# Adafruit_Bluefruit_LE_SPI_Friend.net
KiCad netlist of a schematic drawn in EAGLE
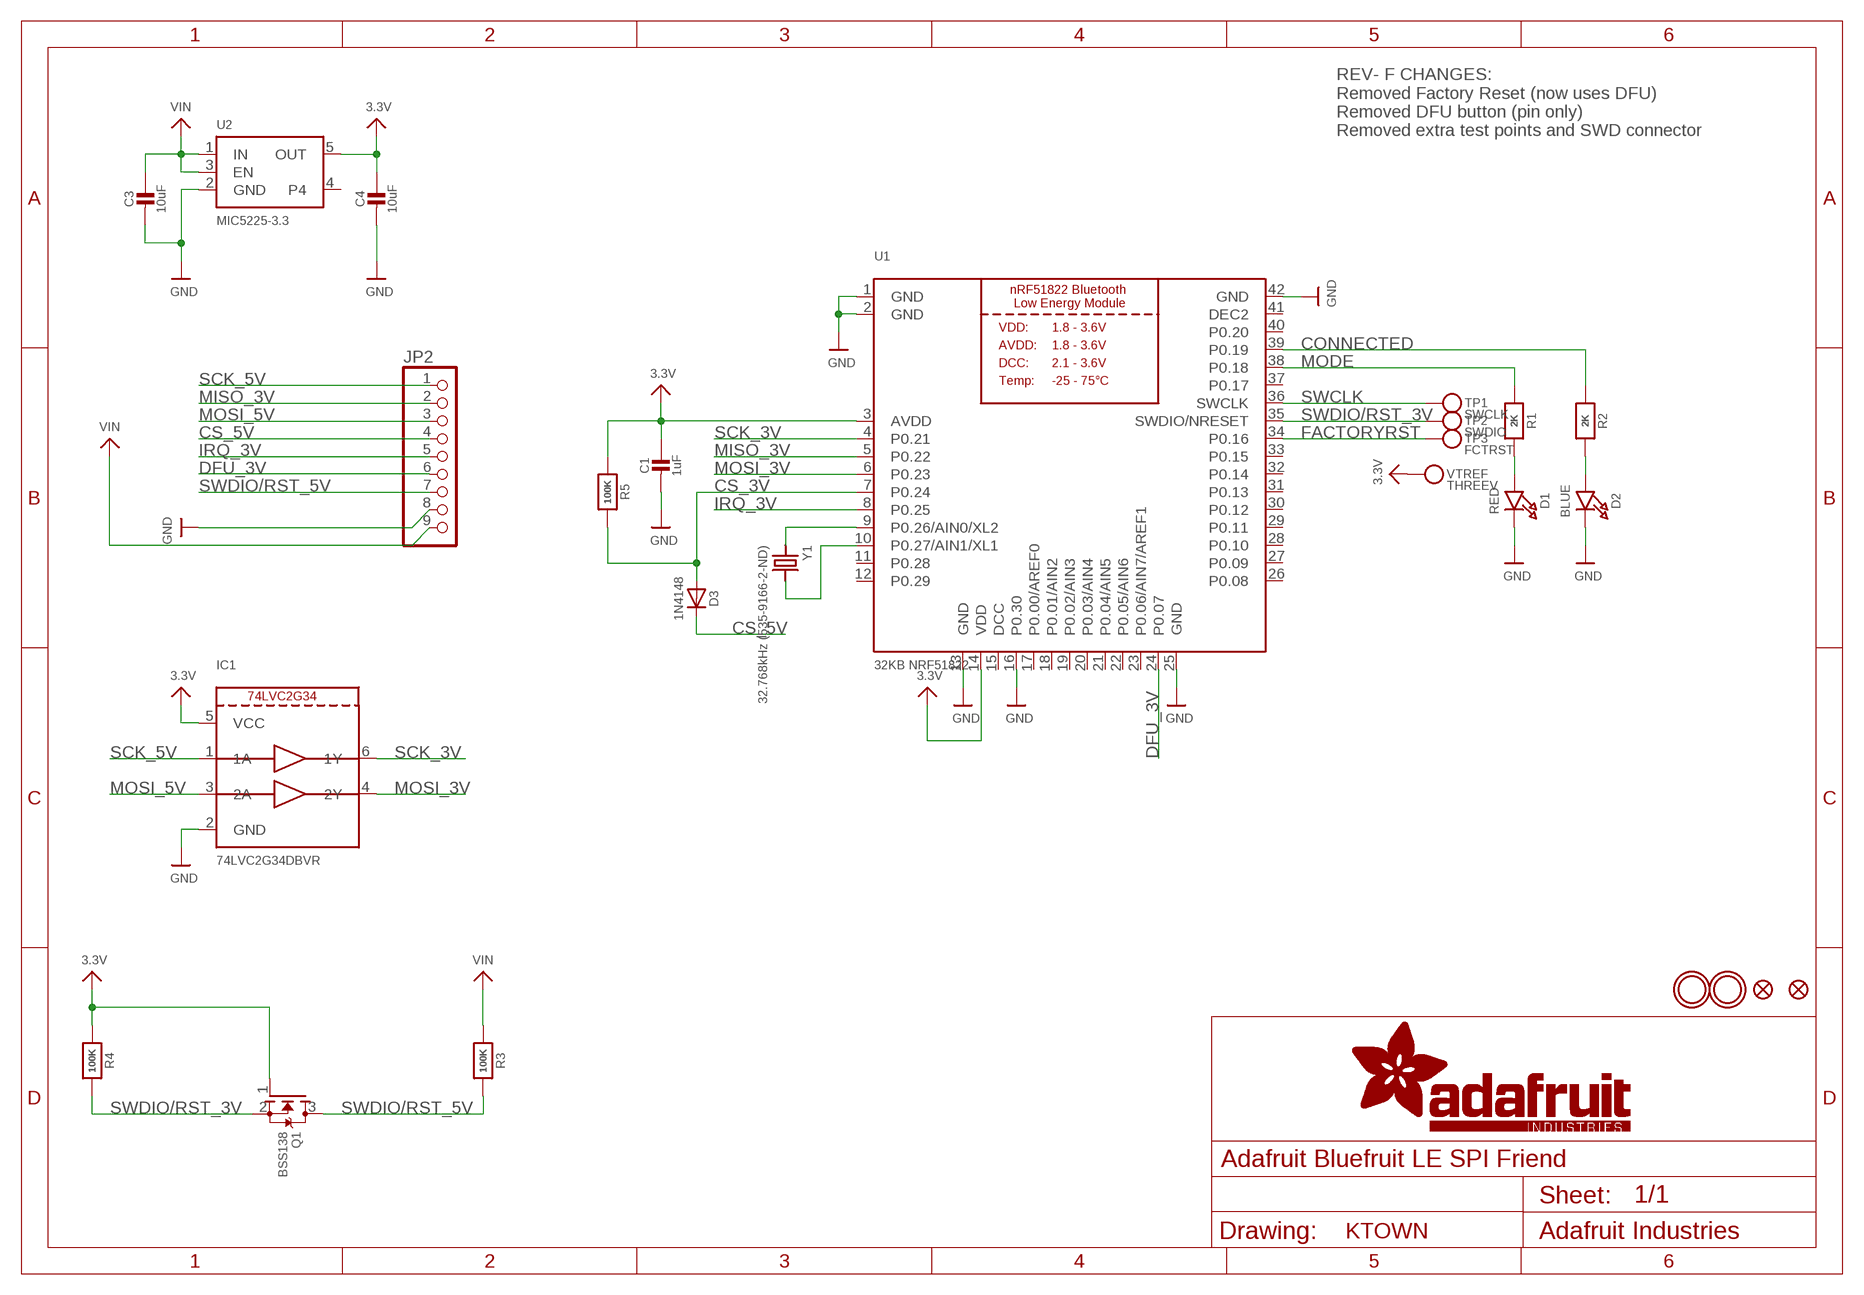
[diagram p0: schematic, sheet 1]

(export (version "E")
  (design (tool "Eeschema 10.0.6"))
  (components
    (comp (ref "C1")
      (value "1uF")
      (footprint "eagle-import:0805_10MGAP")
      (libsource (lib "eagle-import") (part "CAP_CERAMIC0805_10MGAP"))
    )
    (comp (ref "C3")
      (value "10uF")
      (footprint "eagle-import:0805-NO")
      (libsource (lib "eagle-import") (part "CAP_CERAMIC0805-NOOUTLINE"))
    )
    (comp (ref "C4")
      (value "10uF")
      (footprint "eagle-import:0805_10MGAP")
      (libsource (lib "eagle-import") (part "CAP_CERAMIC0805_10MGAP"))
    )
    (comp (ref "D1")
      (value "RED")
      (footprint "eagle-import:CHIPLED_0805_NOOUTLINE")
      (libsource (lib "eagle-import") (part "LED0805_NOOUTLINE"))
    )
    (comp (ref "D2")
      (value "BLUE")
      (footprint "eagle-import:CHIPLED_0805_NOOUTLINE")
      (libsource (lib "eagle-import") (part "LED0805_NOOUTLINE"))
    )
    (comp (ref "D3")
      (value "1N4148")
      (footprint "eagle-import:SOD-323")
      (libsource (lib "eagle-import") (part "DIODESOD-323"))
    )
    (comp (ref "FID1")
      (value "FIDUCIAL\"\"")
      (footprint "eagle-import:FIDUCIAL_1MM")
      (libsource (lib "eagle-import") (part "FIDUCIAL{dblquote}{dblquote}"))
    )
    (comp (ref "FID3")
      (value "FIDUCIAL\"\"")
      (footprint "eagle-import:FIDUCIAL_1MM")
      (libsource (lib "eagle-import") (part "FIDUCIAL{dblquote}{dblquote}"))
    )
    (comp (ref "IC1")
      (value "74LVC2G34DBVR")
      (footprint "eagle-import:SOT23-6")
      (libsource (lib "eagle-import") (part "74LVC2G34DBVR"))
    )
    (comp (ref "JP2")
      (value "HEADER-1X970MIL")
      (footprint "eagle-import:1X09_ROUND_70")
      (libsource (lib "eagle-import") (part "HEADER-1X970MIL"))
    )
    (comp (ref "Q1")
      (value "BSS138")
      (footprint "eagle-import:SOT23-WIDE@1")
      (libsource (lib "eagle-import") (part "MOSFET-NWIDE"))
    )
    (comp (ref "R1")
      (value "2K")
      (footprint "eagle-import:_0805MP")
      (libsource (lib "eagle-import") (part "RESISTOR_0805MP"))
    )
    (comp (ref "R2")
      (value "2K")
      (footprint "eagle-import:_0805MP")
      (libsource (lib "eagle-import") (part "RESISTOR_0805MP"))
    )
    (comp (ref "R3")
      (value "100K")
      (footprint "eagle-import:0805-NO")
      (libsource (lib "eagle-import") (part "RESISTOR0805_NOOUTLINE"))
    )
    (comp (ref "R4")
      (value "100K")
      (footprint "eagle-import:0805-NO")
      (libsource (lib "eagle-import") (part "RESISTOR0805_NOOUTLINE"))
    )
    (comp (ref "R5")
      (value "100K")
      (footprint "eagle-import:_0805MP")
      (libsource (lib "eagle-import") (part "RESISTOR_0805MP"))
    )
    (comp (ref "TP1")
      (value "SWCLK")
      (footprint "eagle-import:PAD-1.5X2.0")
      (libsource (lib "eagle-import") (part "TESTPOINT1.5X2.0MM_NOCREAM"))
    )
    (comp (ref "TP2")
      (value "SWDIO")
      (footprint "eagle-import:PAD-1.5X2.0")
      (libsource (lib "eagle-import") (part "TESTPOINT1.5X2.0MM_NOCREAM"))
    )
    (comp (ref "TP3")
      (value "FCTRST")
      (footprint "eagle-import:PAD-1.5X2.0")
      (libsource (lib "eagle-import") (part "TESTPOINT1.5X2.0MM_NOCREAM"))
    )
    (comp (ref "U$28")
      (value "MOUNTINGHOLE2.5")
      (footprint "eagle-import:MOUNTINGHOLE_2.5_PLATED")
      (libsource (lib "eagle-import") (part "MOUNTINGHOLE2.5"))
    )
    (comp (ref "U$29")
      (value "MOUNTINGHOLE2.5")
      (footprint "eagle-import:MOUNTINGHOLE_2.5_PLATED")
      (libsource (lib "eagle-import") (part "MOUNTINGHOLE2.5"))
    )
    (comp (ref "U1")
      (value "32KB NRF51822")
      (footprint "eagle-import:BLE_MODULE_RAYTAC_MDBT40")
      (libsource (lib "eagle-import") (part "NRF51822_MODULE_MDBT40"))
    )
    (comp (ref "U2")
      (value "MIC5225-3.3")
      (footprint "eagle-import:SOT23-5")
      (libsource (lib "eagle-import") (part "VREG_SOT23-5"))
    )
    (comp (ref "VTREF")
      (value "THREEV")
      (footprint "eagle-import:PAD-1.5X2.0")
      (libsource (lib "eagle-import") (part "TESTPOINT1.5X2.0MM_NOCREAM"))
    )
    (comp (ref "Y1")
      (value "32.768kHz (535-9166-2-ND)")
      (footprint "eagle-import:CRYSTAL_CYL_2X6MM_SMT")
      (libsource (lib "eagle-import") (part "CRYSTAL2.0X6.0_32.768"))
    )
  )
  (nets
    (net (code "1") (name "/CONNECTED") (class "Default")
      (node (ref "R2") (pin "1") (pinfunction "1_1") (pintype "passive"))
      (node (ref "U1") (pin "39") (pinfunction "P0.19_39") (pintype "bidirectional"))
    )
    (net (code "2") (name "/CS_3V") (class "Default")
      (node (ref "D3") (pin "A") (pinfunction "A_A") (pintype "passive"))
      (node (ref "R5") (pin "2") (pinfunction "2_2") (pintype "passive"))
      (node (ref "U1") (pin "7") (pinfunction "P0.24_7") (pintype "bidirectional"))
    )
    (net (code "3") (name "/CS_5V") (class "Default")
      (node (ref "D3") (pin "C") (pinfunction "C_C") (pintype "passive"))
      (node (ref "JP2") (pin "4") (pinfunction "4_4") (pintype "passive"))
    )
    (net (code "4") (name "/DCC") (class "Default")
      (node (ref "U1") (pin "15") (pinfunction "DCC_15") (pintype "power_in"))
    )
    (net (code "5") (name "/DEC2") (class "Default")
      (node (ref "U1") (pin "41") (pinfunction "DEC2_41") (pintype "power_in"))
    )
    (net (code "6") (name "/DFU_3V") (class "Default")
      (node (ref "JP2") (pin "6") (pinfunction "6_6") (pintype "passive"))
      (node (ref "U1") (pin "24") (pinfunction "P0.07_24") (pintype "bidirectional"))
    )
    (net (code "7") (name "/FACTORYRST") (class "Default")
      (node (ref "TP3") (pin "P$1") (pinfunction "P$1_P$1") (pintype "bidirectional"))
      (node (ref "U1") (pin "34") (pinfunction "P0.16_34") (pintype "bidirectional"))
    )
    (net (code "8") (name "/IRQ_3V") (class "Default")
      (node (ref "JP2") (pin "5") (pinfunction "5_5") (pintype "passive"))
      (node (ref "U1") (pin "8") (pinfunction "P0.25_8") (pintype "bidirectional"))
    )
    (net (code "9") (name "/MISO_3V") (class "Default")
      (node (ref "JP2") (pin "2") (pinfunction "2_2") (pintype "passive"))
      (node (ref "U1") (pin "5") (pinfunction "P0.22_5") (pintype "bidirectional"))
    )
    (net (code "10") (name "/MODE") (class "Default")
      (node (ref "R1") (pin "1") (pinfunction "1_1") (pintype "passive"))
      (node (ref "U1") (pin "38") (pinfunction "P0.18_38") (pintype "bidirectional"))
    )
    (net (code "11") (name "/MOSI_3V") (class "Default")
      (node (ref "IC1") (pin "4") (pinfunction "2Y_4") (pintype "output"))
      (node (ref "U1") (pin "6") (pinfunction "P0.23_6") (pintype "bidirectional"))
    )
    (net (code "12") (name "/MOSI_5V") (class "Default")
      (node (ref "IC1") (pin "3") (pinfunction "2A_3") (pintype "input"))
      (node (ref "JP2") (pin "3") (pinfunction "3_3") (pintype "passive"))
    )
    (net (code "13") (name "/SCK_3V") (class "Default")
      (node (ref "IC1") (pin "6") (pinfunction "1Y_6") (pintype "output"))
      (node (ref "U1") (pin "4") (pinfunction "P0.21_4") (pintype "bidirectional"))
    )
    (net (code "14") (name "/SCK_5V") (class "Default")
      (node (ref "IC1") (pin "1") (pinfunction "1A_1") (pintype "input"))
      (node (ref "JP2") (pin "1") (pinfunction "1_1") (pintype "passive"))
    )
    (net (code "15") (name "/SWCLK") (class "Default")
      (node (ref "TP1") (pin "P$1") (pinfunction "P$1_P$1") (pintype "bidirectional"))
      (node (ref "U1") (pin "36") (pinfunction "SWCLK_36") (pintype "bidirectional"))
    )
    (net (code "16") (name "/SWDIO{slash}RST_3V") (class "Default")
      (node (ref "Q1") (pin "2") (pinfunction "S_2") (pintype "bidirectional"))
      (node (ref "R4") (pin "2") (pinfunction "2_2") (pintype "passive"))
      (node (ref "TP2") (pin "P$1") (pinfunction "P$1_P$1") (pintype "bidirectional"))
      (node (ref "U1") (pin "35") (pinfunction "SWDIO/NRESET_35") (pintype "bidirectional"))
    )
    (net (code "17") (name "/SWDIO{slash}RST_5V") (class "Default")
      (node (ref "JP2") (pin "7") (pinfunction "7_7") (pintype "passive"))
      (node (ref "Q1") (pin "3") (pinfunction "D_3") (pintype "bidirectional"))
      (node (ref "R3") (pin "2") (pinfunction "2_2") (pintype "passive"))
    )
    (net (code "18") (name "3.3V") (class "Default")
      (node (ref "C1") (pin "1") (pinfunction "1_1") (pintype "passive"))
      (node (ref "C4") (pin "1") (pinfunction "1_1") (pintype "passive"))
      (node (ref "IC1") (pin "5") (pinfunction "VCC_5") (pintype "power_in"))
      (node (ref "Q1") (pin "1") (pinfunction "G_1") (pintype "bidirectional"))
      (node (ref "R4") (pin "1") (pinfunction "1_1") (pintype "passive"))
      (node (ref "R5") (pin "1") (pinfunction "1_1") (pintype "passive"))
      (node (ref "U1") (pin "14") (pinfunction "VDD_14") (pintype "power_in"))
      (node (ref "U1") (pin "3") (pinfunction "AVDD_3") (pintype "power_in"))
      (node (ref "U2") (pin "5") (pinfunction "OUT_5") (pintype "power_in"))
      (node (ref "VTREF") (pin "P$1") (pinfunction "P$1_P$1") (pintype "bidirectional"))
    )
    (net (code "19") (name "GND") (class "Default")
      (node (ref "C1") (pin "2") (pinfunction "2_2") (pintype "passive"))
      (node (ref "C3") (pin "2") (pinfunction "2_2") (pintype "passive"))
      (node (ref "C4") (pin "2") (pinfunction "2_2") (pintype "passive"))
      (node (ref "D1") (pin "C") (pinfunction "C_C") (pintype "passive"))
      (node (ref "D2") (pin "C") (pinfunction "C_C") (pintype "passive"))
      (node (ref "IC1") (pin "2") (pinfunction "GND_2") (pintype "power_in"))
      (node (ref "JP2") (pin "8") (pinfunction "8_8") (pintype "passive"))
      (node (ref "U1") (pin "1") (pinfunction "GND_1") (pintype "power_in"))
      (node (ref "U1") (pin "13") (pinfunction "GND_13") (pintype "power_in"))
      (node (ref "U1") (pin "16") (pinfunction "P0.30_16") (pintype "bidirectional"))
      (node (ref "U1") (pin "2") (pinfunction "GND_2") (pintype "power_in"))
      (node (ref "U1") (pin "25") (pinfunction "GND_25") (pintype "power_in"))
      (node (ref "U1") (pin "42") (pinfunction "GND_42") (pintype "power_in"))
      (node (ref "U2") (pin "2") (pinfunction "GND_2") (pintype "power_in"))
    )
    (net (code "20") (name "Net-(D1-PadA)") (class "Default")
      (node (ref "D1") (pin "A") (pinfunction "A_A") (pintype "passive"))
      (node (ref "R1") (pin "2") (pinfunction "2_2") (pintype "passive"))
    )
    (net (code "21") (name "Net-(D2-PadA)") (class "Default")
      (node (ref "D2") (pin "A") (pinfunction "A_A") (pintype "passive"))
      (node (ref "R2") (pin "2") (pinfunction "2_2") (pintype "passive"))
    )
    (net (code "22") (name "Net-(U1-P0.26{slash}AIN0{slash}XL2)") (class "Default")
      (node (ref "U1") (pin "9") (pinfunction "P0.26/AIN0/XL2_9") (pintype "bidirectional"))
      (node (ref "Y1") (pin "1") (pinfunction "1_1") (pintype "passive"))
    )
    (net (code "23") (name "Net-(U1-P0.27{slash}AIN1{slash}XL1)") (class "Default")
      (node (ref "U1") (pin "10") (pinfunction "P0.27/AIN1/XL1_10") (pintype "bidirectional"))
      (node (ref "Y1") (pin "2") (pinfunction "2_2") (pintype "passive"))
    )
    (net (code "24") (name "VIN") (class "Default")
      (node (ref "C3") (pin "1") (pinfunction "1_1") (pintype "passive"))
      (node (ref "JP2") (pin "9") (pinfunction "9_9") (pintype "passive"))
      (node (ref "R3") (pin "1") (pinfunction "1_1") (pintype "passive"))
      (node (ref "U2") (pin "1") (pinfunction "IN_1") (pintype "power_in"))
      (node (ref "U2") (pin "3") (pinfunction "EN_3") (pintype "input"))
    )
    (net (code "25") (name "unconnected-(U1-P0.00{slash}AREF0-Pad17)") (class "Default")
      (node (ref "U1") (pin "17") (pinfunction "P0.00/AREF0_17") (pintype "bidirectional"))
    )
    (net (code "26") (name "unconnected-(U1-P0.01{slash}AIN2-Pad18)") (class "Default")
      (node (ref "U1") (pin "18") (pinfunction "P0.01/AIN2_18") (pintype "bidirectional"))
    )
    (net (code "27") (name "unconnected-(U1-P0.02{slash}AIN3-Pad19)") (class "Default")
      (node (ref "U1") (pin "19") (pinfunction "P0.02/AIN3_19") (pintype "bidirectional"))
    )
    (net (code "28") (name "unconnected-(U1-P0.03{slash}AIN4-Pad20)") (class "Default")
      (node (ref "U1") (pin "20") (pinfunction "P0.03/AIN4_20") (pintype "bidirectional"))
    )
    (net (code "29") (name "unconnected-(U1-P0.04{slash}AIN5-Pad21)") (class "Default")
      (node (ref "U1") (pin "21") (pinfunction "P0.04/AIN5_21") (pintype "bidirectional"))
    )
    (net (code "30") (name "unconnected-(U1-P0.05{slash}AIN6-Pad22)") (class "Default")
      (node (ref "U1") (pin "22") (pinfunction "P0.05/AIN6_22") (pintype "bidirectional"))
    )
    (net (code "31") (name "unconnected-(U1-P0.06{slash}AIN7{slash}AREF1-Pad23)") (class "Default")
      (node (ref "U1") (pin "23") (pinfunction "P0.06/AIN7/AREF1_23") (pintype "bidirectional"))
    )
    (net (code "32") (name "unconnected-(U1-P0.08-Pad26)") (class "Default")
      (node (ref "U1") (pin "26") (pinfunction "P0.08_26") (pintype "bidirectional"))
    )
    (net (code "33") (name "unconnected-(U1-P0.09-Pad27)") (class "Default")
      (node (ref "U1") (pin "27") (pinfunction "P0.09_27") (pintype "bidirectional"))
    )
    (net (code "34") (name "unconnected-(U1-P0.10-Pad28)") (class "Default")
      (node (ref "U1") (pin "28") (pinfunction "P0.10_28") (pintype "bidirectional"))
    )
    (net (code "35") (name "unconnected-(U1-P0.11-Pad29)") (class "Default")
      (node (ref "U1") (pin "29") (pinfunction "P0.11_29") (pintype "bidirectional"))
    )
    (net (code "36") (name "unconnected-(U1-P0.12-Pad30)") (class "Default")
      (node (ref "U1") (pin "30") (pinfunction "P0.12_30") (pintype "bidirectional"))
    )
    (net (code "37") (name "unconnected-(U1-P0.13-Pad31)") (class "Default")
      (node (ref "U1") (pin "31") (pinfunction "P0.13_31") (pintype "bidirectional"))
    )
    (net (code "38") (name "unconnected-(U1-P0.14-Pad32)") (class "Default")
      (node (ref "U1") (pin "32") (pinfunction "P0.14_32") (pintype "bidirectional"))
    )
    (net (code "39") (name "unconnected-(U1-P0.15-Pad33)") (class "Default")
      (node (ref "U1") (pin "33") (pinfunction "P0.15_33") (pintype "bidirectional"))
    )
    (net (code "40") (name "unconnected-(U1-P0.17-Pad37)") (class "Default")
      (node (ref "U1") (pin "37") (pinfunction "P0.17_37") (pintype "bidirectional"))
    )
    (net (code "41") (name "unconnected-(U1-P0.20-Pad40)") (class "Default")
      (node (ref "U1") (pin "40") (pinfunction "P0.20_40") (pintype "bidirectional"))
    )
    (net (code "42") (name "unconnected-(U1-P0.28-Pad11)") (class "Default")
      (node (ref "U1") (pin "11") (pinfunction "P0.28_11") (pintype "bidirectional"))
    )
    (net (code "43") (name "unconnected-(U1-P0.29-Pad12)") (class "Default")
      (node (ref "U1") (pin "12") (pinfunction "P0.29_12") (pintype "bidirectional"))
    )
    (net (code "44") (name "unconnected-(U2-P4-Pad4)") (class "Default")
      (node (ref "U2") (pin "4") (pinfunction "P4_4") (pintype "bidirectional"))
    )
  )
)
